# iTag4Sensors2.net
KiCad netlist of a schematic drawn in Altium Designer
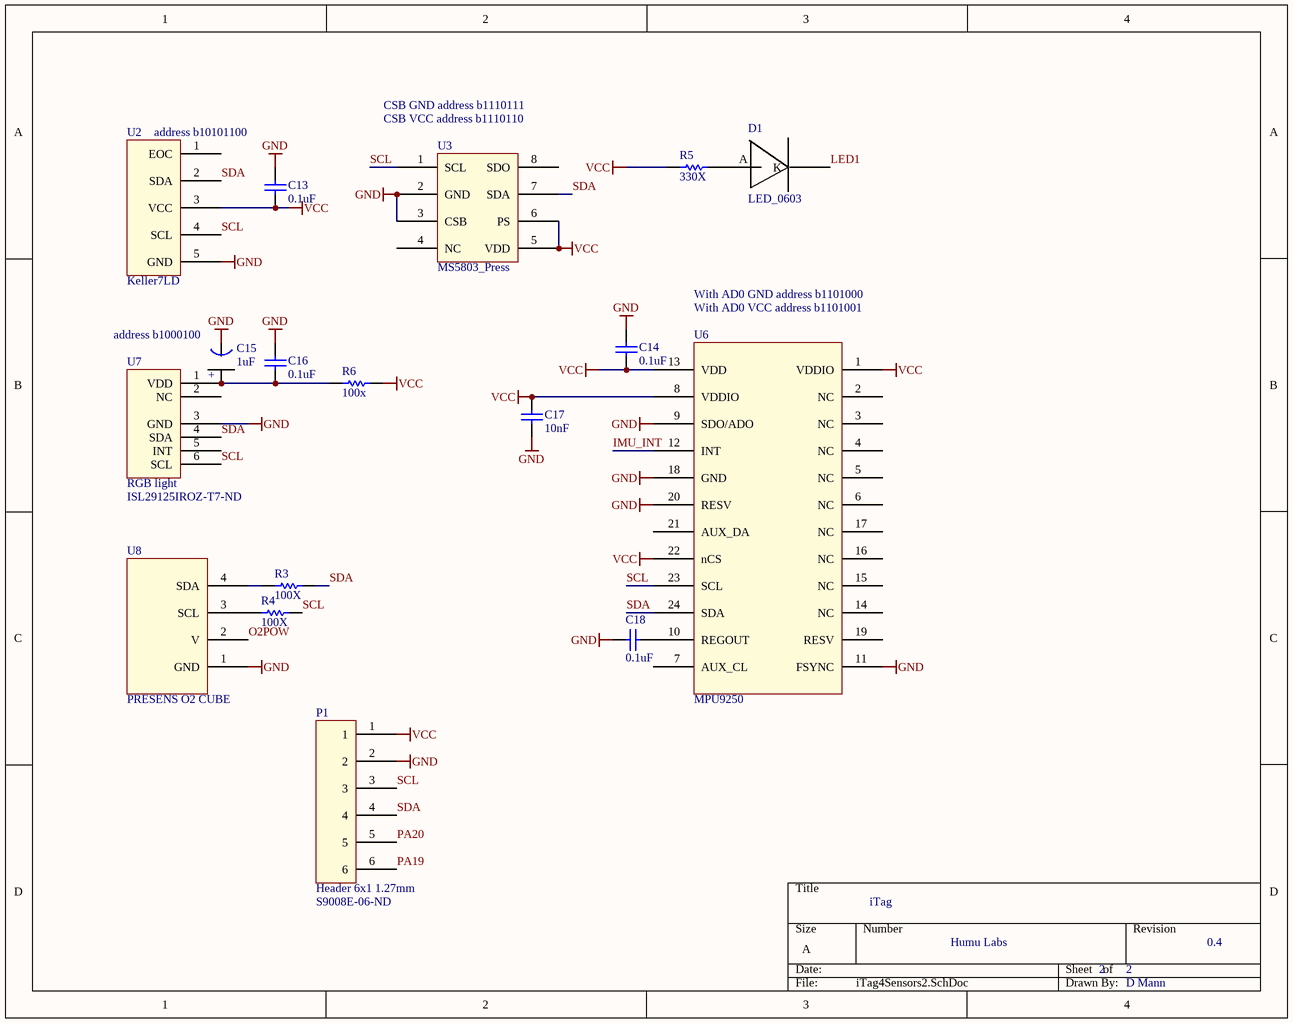
[diagram p0: iTag4Sensors2.SchDoc]

(export (version "E")
  (design (tool "Eeschema 10.0.6"))
  (components
    (comp (ref "C13")
      (value "0.1uF")
      (footprint "0402")
      (description "Ceramic Chip Capacitor - Standard")
      (fields (field (name "PUBLISHER") "Altium Limited"))
      (libsource (lib "KEMET Chip Capacitor") (part "C0402"))
    )
    (comp (ref "C14")
      (value "0.1uF")
      (footprint "0402")
      (description "Ceramic Chip Capacitor - Standard")
      (fields (field (name "PUBLISHER") "Altium Limited"))
      (libsource (lib "KEMET Chip Capacitor") (part "C0402"))
    )
    (comp (ref "C15") (value "1uF") (footprint "Tant0805") (libsource (lib "Loggerhead") (part "Tant0805")))
    (comp (ref "C16")
      (value "0.1uF")
      (footprint "0402")
      (description "Ceramic Chip Capacitor - Standard")
      (fields (field (name "PUBLISHER") "Altium Limited"))
      (libsource (lib "KEMET Chip Capacitor") (part "C0402"))
    )
    (comp (ref "C17")
      (value "10nF")
      (footprint "0402")
      (description "Ceramic Chip Capacitor - Standard")
      (fields (field (name "PUBLISHER") "Altium Limited"))
      (libsource (lib "KEMET Chip Capacitor") (part "C0402"))
    )
    (comp (ref "C18")
      (value "0.1uF")
      (footprint "0402")
      (description "Ceramic Chip Capacitor - Standard")
      (fields (field (name "PUBLISHER") "Altium Limited"))
      (libsource (lib "KEMET Chip Capacitor") (part "C0402"))
    )
    (comp (ref "D1")
      (value "LED_0603")
      (footprint "Diode0603")
      (libsource (lib "Loggerhead") (part "LED_0603"))
    )
    (comp (ref "P1")
      (value "Header 6x1 1.27mm")
      (footprint "Header6x1 1.27mm")
      (fields (field (name "SUPPLIER PART NUMBER 1") "S9008E-06-ND"))
      (libsource (lib "Loggerhead") (part "Header 6x1 1.27mm"))
    )
    (comp (ref "R3")
      (value "100X")
      (footprint "3-0603")
      (fields (field (name "PUBLISHER") "Altium Limited"))
      (libsource (lib "Panasonic Resistor") (part "ERJ3RK"))
    )
    (comp (ref "R4")
      (value "100X")
      (footprint "3-0603")
      (fields (field (name "PUBLISHER") "Altium Limited"))
      (libsource (lib "Panasonic Resistor") (part "ERJ3RK"))
    )
    (comp (ref "R5")
      (value "330X")
      (footprint "3-0603")
      (fields (field (name "PUBLISHER") "Altium Limited"))
      (libsource (lib "Panasonic Resistor") (part "ERJ3RK"))
    )
    (comp (ref "R6")
      (value "100x")
      (footprint "3-0603")
      (fields (field (name "PUBLISHER") "Altium Limited"))
      (libsource (lib "Panasonic Resistor") (part "ERJ3RK"))
    )
    (comp (ref "U2")
      (value "Keller7LD")
      (footprint "Keller7LD")
      (description "Keller Pressure/Temp")
      (libsource (lib "Loggerhead") (part "Keller 7LD"))
    )
    (comp (ref "U3")
      (value "MS5803_Press")
      (footprint "MS5803_Press")
      (libsource (lib "Loggerhead") (part "MS5803_Press"))
    )
    (comp (ref "U6")
      (value "MPU9250")
      (footprint "MPU6500")
      (description "Invensense")
      (libsource (lib "Loggerhead") (part "MPU-9250"))
    )
    (comp (ref "U7")
      (value "RGB light")
      (footprint "ODFN")
      (description "RGB light sensor")
      (fields (field (name "SUPPLIER PART NUMBER 1") "ISL29125IROZ-T7-ND"))
      (libsource (lib "Loggerhead") (part "ISL29125"))
    )
    (comp (ref "U8")
      (value "PRESENS O2 CUBE")
      (footprint "PRESENS_O2")
      (libsource (lib "Loggerhead") (part "PRESENS_O2"))
    )
  )
  (nets
    (net (code "1") (name "/IMU_INT") (class "Default")
      (node (ref "U6") (pin "12") (pinfunction "INT_12") (pintype "passive"))
    )
    (net (code "2") (name "/LED1") (class "Default")
      (node (ref "D1") (pin "K") (pinfunction "K_K") (pintype "passive"))
    )
    (net (code "3") (name "/O2POW") (class "Default")
      (node (ref "U8") (pin "2") (pinfunction "V_2") (pintype "passive"))
    )
    (net (code "4") (name "/PA19") (class "Default")
      (node (ref "P1") (pin "6") (pinfunction "6_6") (pintype "passive"))
    )
    (net (code "5") (name "/PA20") (class "Default")
      (node (ref "P1") (pin "5") (pinfunction "5_5") (pintype "passive"))
    )
    (net (code "6") (name "/SCL") (class "Default")
      (node (ref "P1") (pin "3") (pinfunction "3_3") (pintype "passive"))
      (node (ref "R4") (pin "2") (pinfunction "2_2") (pintype "passive"))
      (node (ref "U2") (pin "4") (pinfunction "SCL_4") (pintype "passive"))
      (node (ref "U3") (pin "1") (pinfunction "SCL_1") (pintype "passive"))
      (node (ref "U6") (pin "23") (pinfunction "SCL_23") (pintype "passive"))
      (node (ref "U7") (pin "6") (pinfunction "SCL_6") (pintype "passive"))
    )
    (net (code "7") (name "/SDA") (class "Default")
      (node (ref "P1") (pin "4") (pinfunction "4_4") (pintype "passive"))
      (node (ref "R3") (pin "2") (pinfunction "2_2") (pintype "passive"))
      (node (ref "U2") (pin "2") (pinfunction "SDA_2") (pintype "passive"))
      (node (ref "U3") (pin "7") (pinfunction "SDA_7") (pintype "passive"))
      (node (ref "U6") (pin "24") (pinfunction "SDA_24") (pintype "passive"))
      (node (ref "U7") (pin "4") (pinfunction "SDA_4") (pintype "passive"))
    )
    (net (code "8") (name "GND") (class "Default")
      (node (ref "C13") (pin "2") (pinfunction "2_2") (pintype "passive"))
      (node (ref "C14") (pin "2") (pinfunction "2_2") (pintype "passive"))
      (node (ref "C15") (pin "1") (pinfunction "GND_1") (pintype "passive"))
      (node (ref "C16") (pin "2") (pinfunction "2_2") (pintype "passive"))
      (node (ref "C17") (pin "2") (pinfunction "2_2") (pintype "passive"))
      (node (ref "C18") (pin "1") (pinfunction "1_1") (pintype "passive"))
      (node (ref "P1") (pin "2") (pinfunction "2_2") (pintype "passive"))
      (node (ref "U2") (pin "5") (pinfunction "GND_5") (pintype "passive"))
      (node (ref "U3") (pin "2") (pinfunction "GND_2") (pintype "passive"))
      (node (ref "U3") (pin "3") (pinfunction "CSB_3") (pintype "passive"))
      (node (ref "U6") (pin "11") (pinfunction "FSYNC_11") (pintype "passive"))
      (node (ref "U6") (pin "18") (pinfunction "GND_18") (pintype "passive"))
      (node (ref "U6") (pin "20") (pinfunction "RESV_20") (pintype "passive"))
      (node (ref "U6") (pin "9") (pinfunction "SDO/ADO_9") (pintype "passive"))
      (node (ref "U7") (pin "3") (pinfunction "GND_3") (pintype "passive"))
      (node (ref "U8") (pin "1") (pinfunction "GND_1") (pintype "passive"))
    )
    (net (code "9") (name "Net-(C15-+)") (class "Default")
      (node (ref "C15") (pin "2") (pinfunction "+_2") (pintype "passive"))
      (node (ref "C16") (pin "1") (pinfunction "1_1") (pintype "passive"))
      (node (ref "R6") (pin "2") (pinfunction "2_2") (pintype "passive"))
      (node (ref "U7") (pin "1") (pinfunction "VDD_1") (pintype "passive"))
    )
    (net (code "10") (name "Net-(D1-PadA)") (class "Default")
      (node (ref "D1") (pin "A") (pinfunction "A_A") (pintype "passive"))
      (node (ref "R5") (pin "2") (pinfunction "2_2") (pintype "passive"))
    )
    (net (code "11") (name "Net-(U6-REGOUT)") (class "Default")
      (node (ref "C18") (pin "2") (pinfunction "2_2") (pintype "passive"))
      (node (ref "U6") (pin "10") (pinfunction "REGOUT_10") (pintype "passive"))
    )
    (net (code "12") (name "Net-(U8-SCL)") (class "Default")
      (node (ref "R4") (pin "1") (pinfunction "1_1") (pintype "passive"))
      (node (ref "U8") (pin "3") (pinfunction "SCL_3") (pintype "passive"))
    )
    (net (code "13") (name "Net-(U8-SDA)") (class "Default")
      (node (ref "R3") (pin "1") (pinfunction "1_1") (pintype "passive"))
      (node (ref "U8") (pin "4") (pinfunction "SDA_4") (pintype "passive"))
    )
    (net (code "14") (name "VCC") (class "Default")
      (node (ref "C13") (pin "1") (pinfunction "1_1") (pintype "passive"))
      (node (ref "C14") (pin "1") (pinfunction "1_1") (pintype "passive"))
      (node (ref "C17") (pin "1") (pinfunction "1_1") (pintype "passive"))
      (node (ref "P1") (pin "1") (pinfunction "1_1") (pintype "passive"))
      (node (ref "R5") (pin "1") (pinfunction "1_1") (pintype "passive"))
      (node (ref "R6") (pin "1") (pinfunction "1_1") (pintype "passive"))
      (node (ref "U2") (pin "3") (pinfunction "VCC_3") (pintype "passive"))
      (node (ref "U3") (pin "5") (pinfunction "VDD_5") (pintype "power_in"))
      (node (ref "U3") (pin "6") (pinfunction "PS_6") (pintype "passive"))
      (node (ref "U6") (pin "1") (pinfunction "VDDIO_1") (pintype "passive"))
      (node (ref "U6") (pin "13") (pinfunction "VDD_13") (pintype "passive"))
      (node (ref "U6") (pin "22") (pinfunction "nCS_22") (pintype "passive"))
      (node (ref "U6") (pin "8") (pinfunction "VDDIO_8") (pintype "passive"))
    )
    (net (code "15") (name "unconnected-(U2-EOC-Pad1)") (class "Default")
      (node (ref "U2") (pin "1") (pinfunction "EOC_1") (pintype "passive"))
    )
    (net (code "16") (name "unconnected-(U3-NC-Pad4)") (class "Default")
      (node (ref "U3") (pin "4") (pinfunction "NC_4") (pintype "passive"))
    )
    (net (code "17") (name "unconnected-(U3-SDO-Pad8)") (class "Default")
      (node (ref "U3") (pin "8") (pinfunction "SDO_8") (pintype "passive"))
    )
    (net (code "18") (name "unconnected-(U6-AUX_CL-Pad7)") (class "Default")
      (node (ref "U6") (pin "7") (pinfunction "AUX_CL_7") (pintype "passive"))
    )
    (net (code "19") (name "unconnected-(U6-AUX_DA-Pad21)") (class "Default")
      (node (ref "U6") (pin "21") (pinfunction "AUX_DA_21") (pintype "passive"))
    )
    (net (code "20") (name "unconnected-(U6-NC-Pad2)") (class "Default")
      (node (ref "U6") (pin "2") (pinfunction "NC_2") (pintype "passive"))
    )
    (net (code "21") (name "unconnected-(U6-NC-Pad3)") (class "Default")
      (node (ref "U6") (pin "3") (pinfunction "NC_3") (pintype "passive"))
    )
    (net (code "22") (name "unconnected-(U6-NC-Pad4)") (class "Default")
      (node (ref "U6") (pin "4") (pinfunction "NC_4") (pintype "passive"))
    )
    (net (code "23") (name "unconnected-(U6-NC-Pad5)") (class "Default")
      (node (ref "U6") (pin "5") (pinfunction "NC_5") (pintype "passive"))
    )
    (net (code "24") (name "unconnected-(U6-NC-Pad6)") (class "Default")
      (node (ref "U6") (pin "6") (pinfunction "NC_6") (pintype "passive"))
    )
    (net (code "25") (name "unconnected-(U6-NC-Pad14)") (class "Default")
      (node (ref "U6") (pin "14") (pinfunction "NC_14") (pintype "passive"))
    )
    (net (code "26") (name "unconnected-(U6-NC-Pad15)") (class "Default")
      (node (ref "U6") (pin "15") (pinfunction "NC_15") (pintype "passive"))
    )
    (net (code "27") (name "unconnected-(U6-NC-Pad16)") (class "Default")
      (node (ref "U6") (pin "16") (pinfunction "NC_16") (pintype "passive"))
    )
    (net (code "28") (name "unconnected-(U6-NC-Pad17)") (class "Default")
      (node (ref "U6") (pin "17") (pinfunction "NC_17") (pintype "passive"))
    )
    (net (code "29") (name "unconnected-(U6-RESV-Pad19)") (class "Default")
      (node (ref "U6") (pin "19") (pinfunction "RESV_19") (pintype "passive"))
    )
    (net (code "30") (name "unconnected-(U7-INT-Pad5)") (class "Default")
      (node (ref "U7") (pin "5") (pinfunction "INT_5") (pintype "passive"))
    )
    (net (code "31") (name "unconnected-(U7-NC-Pad2)") (class "Default")
      (node (ref "U7") (pin "2") (pinfunction "NC_2") (pintype "passive"))
    )
  )
)
